# design.net
KiCad netlist of a schematic drawn in Altium Designer
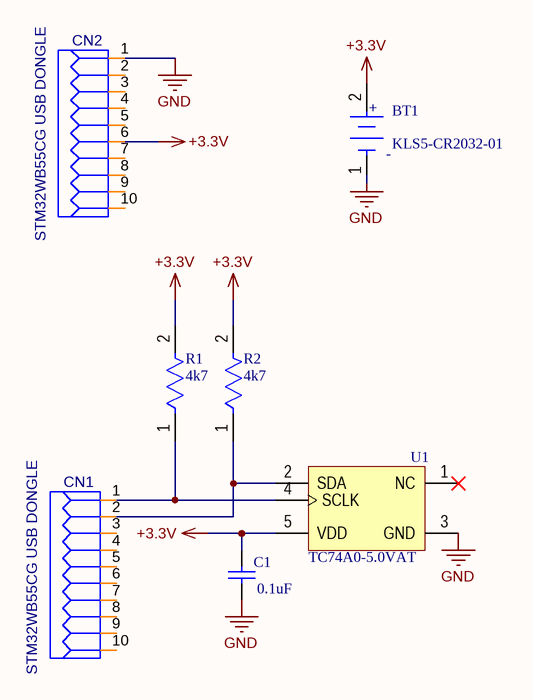
[diagram p0: Схема принципиальная.SchDoc]

(export (version "E")
  (design (tool "Eeschema 10.0.6"))
  (components
    (comp (ref "BT1")
      (value "KLS5-CR2032-01")
      (footprint "FP-BU2032SM-HD-G-MFG")
      (libsource (lib "Altium Content Vault") (part "60d3b5b901a8747834971d0eb8cf3fd"))
    )
    (comp (ref "C1")
      (value "0.1uF")
      (footprint "CAPC2013X140X45NL15T25")
      (description "GRM21BR71H104K\r\n0.1 мкФ X7R 10% 50В 0805")
      (fields (field (name "PART NUMBER") "GRM21BR71C475KA73L") (field (name "MANUFACTURER") "Murata"))
      (libsource (lib "Altium Content Vault") (part "CAP"))
    )
    (comp (ref "CN1")
      (value "PBS-10")
      (footprint "PBS-10")
      (description "2.54mm")
      (fields (field (name "PUBLISHER") "Catcatcat Electronics"))
      (libsource (lib "Connectors") (part "PBS-10"))
    )
    (comp (ref "CN2")
      (value "PBS-10")
      (footprint "PBS-10")
      (description "2.54mm")
      (fields (field (name "PUBLISHER") "Catcatcat Electronics"))
      (libsource (lib "Connectors") (part "PBS-10"))
    )
    (comp (ref "R1")
      (value "4k7")
      (footprint "FP-CR0805-IPC_C")
      (description "0805 300kΩ 0.125W 1%")
      (fields (field (name "TOLERANCE") "1%"))
      (libsource (lib "Altium Content Vault") (part "1029c3af85768c4190bb7ad29bc67b5"))
    )
    (comp (ref "R2")
      (value "4k7")
      (footprint "FP-CR0805-IPC_C")
      (description "0805 300kΩ 0.125W 1%")
      (fields (field (name "TOLERANCE") "1%"))
      (libsource (lib "Altium Content Vault") (part "1029c3af85768c4190bb7ad29bc67b5"))
    )
    (comp (ref "U1")
      (value "TC74A0-5.0VAT")
      (footprint "TO-220-AT5")
      (description "Tiny Serial Digital Thermal Sensor, 5-Pin TO-220, Extended Temperature")
      (libsource (lib "Altium Content Vault") (part "SEN-TEMP-TC74-5"))
    )
  )
  (nets
    (net (code "1") (name "+3.3V") (class "Default")
      (node (ref "BT1") (pin "2") (pinfunction "A_2") (pintype "passive"))
      (node (ref "C1") (pin "2") (pinfunction "2_2") (pintype "passive"))
      (node (ref "CN2") (pin "6") (pinfunction "6_6") (pintype "passive"))
      (node (ref "R1") (pin "2") (pinfunction "2_2") (pintype "passive"))
      (node (ref "R2") (pin "2") (pinfunction "2_2") (pintype "passive"))
      (node (ref "U1") (pin "5") (pinfunction "VDD_5") (pintype "power_in"))
    )
    (net (code "2") (name "GND") (class "Default")
      (node (ref "BT1") (pin "1") (pinfunction "C_1") (pintype "passive"))
      (node (ref "C1") (pin "1") (pinfunction "1_1") (pintype "passive"))
      (node (ref "CN2") (pin "1") (pinfunction "1_1") (pintype "passive"))
      (node (ref "U1") (pin "3") (pinfunction "GND_3") (pintype "power_in"))
    )
    (net (code "3") (name "Net-(U1-SCLK)") (class "Default")
      (node (ref "CN1") (pin "1") (pinfunction "1_1") (pintype "passive"))
      (node (ref "R1") (pin "1") (pinfunction "1_1") (pintype "passive"))
      (node (ref "U1") (pin "4") (pinfunction "SCLK_4") (pintype "passive"))
    )
    (net (code "4") (name "Net-(U1-SDA)") (class "Default")
      (node (ref "CN1") (pin "2") (pinfunction "2_2") (pintype "passive"))
      (node (ref "R2") (pin "1") (pinfunction "1_1") (pintype "passive"))
      (node (ref "U1") (pin "2") (pinfunction "SDA_2") (pintype "passive"))
    )
    (net (code "5") (name "unconnected-(CN1-Pad3)") (class "Default")
      (node (ref "CN1") (pin "3") (pinfunction "3_3") (pintype "passive"))
    )
    (net (code "6") (name "unconnected-(CN1-Pad4)") (class "Default")
      (node (ref "CN1") (pin "4") (pinfunction "4_4") (pintype "passive"))
    )
    (net (code "7") (name "unconnected-(CN1-Pad5)") (class "Default")
      (node (ref "CN1") (pin "5") (pinfunction "5_5") (pintype "passive"))
    )
    (net (code "8") (name "unconnected-(CN1-Pad6)") (class "Default")
      (node (ref "CN1") (pin "6") (pinfunction "6_6") (pintype "passive"))
    )
    (net (code "9") (name "unconnected-(CN1-Pad7)") (class "Default")
      (node (ref "CN1") (pin "7") (pinfunction "7_7") (pintype "passive"))
    )
    (net (code "10") (name "unconnected-(CN1-Pad8)") (class "Default")
      (node (ref "CN1") (pin "8") (pinfunction "8_8") (pintype "passive"))
    )
    (net (code "11") (name "unconnected-(CN1-Pad9)") (class "Default")
      (node (ref "CN1") (pin "9") (pinfunction "9_9") (pintype "passive"))
    )
    (net (code "12") (name "unconnected-(CN1-Pad10)") (class "Default")
      (node (ref "CN1") (pin "10") (pinfunction "10_10") (pintype "passive"))
    )
    (net (code "13") (name "unconnected-(CN2-Pad2)") (class "Default")
      (node (ref "CN2") (pin "2") (pinfunction "2_2") (pintype "passive"))
    )
    (net (code "14") (name "unconnected-(CN2-Pad3)") (class "Default")
      (node (ref "CN2") (pin "3") (pinfunction "3_3") (pintype "passive"))
    )
    (net (code "15") (name "unconnected-(CN2-Pad4)") (class "Default")
      (node (ref "CN2") (pin "4") (pinfunction "4_4") (pintype "passive"))
    )
    (net (code "16") (name "unconnected-(CN2-Pad5)") (class "Default")
      (node (ref "CN2") (pin "5") (pinfunction "5_5") (pintype "passive"))
    )
    (net (code "17") (name "unconnected-(CN2-Pad7)") (class "Default")
      (node (ref "CN2") (pin "7") (pinfunction "7_7") (pintype "passive"))
    )
    (net (code "18") (name "unconnected-(CN2-Pad8)") (class "Default")
      (node (ref "CN2") (pin "8") (pinfunction "8_8") (pintype "passive"))
    )
    (net (code "19") (name "unconnected-(CN2-Pad9)") (class "Default")
      (node (ref "CN2") (pin "9") (pinfunction "9_9") (pintype "passive"))
    )
    (net (code "20") (name "unconnected-(CN2-Pad10)") (class "Default")
      (node (ref "CN2") (pin "10") (pinfunction "10_10") (pintype "passive"))
    )
    (net (code "21") (name "unconnected-(U1-NC-Pad1)") (class "Default")
      (node (ref "U1") (pin "1") (pinfunction "NC_1") (pintype "passive+no_connect"))
    )
  )
)
